# EXP02_04_2307_20232241110.net
KiCad netlist of a schematic drawn in Altium Designer
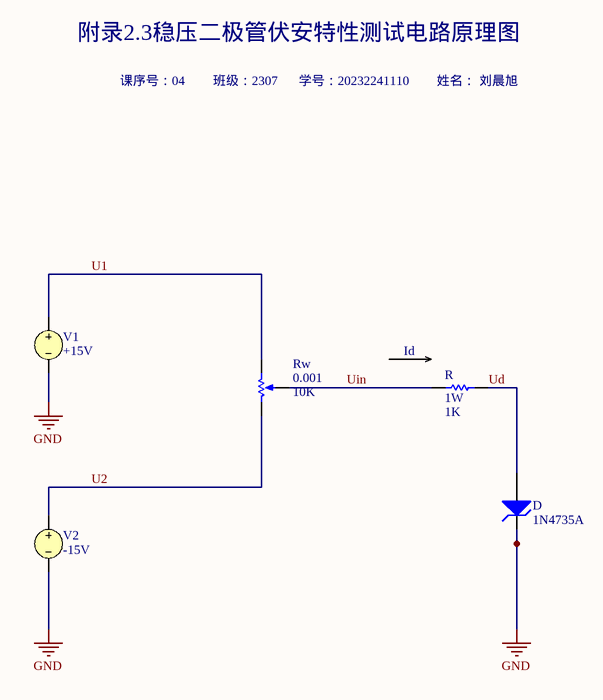
[diagram p0: EXP02_04_2307_20232241110.SchDoc]

(export (version "E")
  (design (tool "Eeschema 10.0.6"))
  (components
    (comp (ref "D")
      (value "1N4735A")
      (footprint "DO-41")
      (description "One Watt Zener")
      (fields (field (name "PUBLISHER") "Altium Limited"))
      (libsource (lib "FSC Discrete Diode") (part "1N4735A"))
    )
    (comp (ref "R")
      (value "1W")
      (footprint "AXIAL-0.3")
      (description "Resistor")
      (fields (field (name "ALTIUM_VALUE") "1K") (field (name "PUBLISHER") "Altium Limited"))
      (libsource (lib "Miscellaneous Devices") (part "Res1"))
    )
    (comp (ref "Rw")
      (value "10K")
      (footprint "VR5")
      (description "Potentiometer")
      (fields
        (field (name "SET POSITION") "0.001")
        (field (name "Comment") "RPot")
        (field (name "PUBLISHER") "Altium Limited")
      )
      (libsource (lib "Miscellaneous Devices") (part "RPot"))
    )
    (comp (ref "V1")
      (value "+15V")
      (description "Voltage Source")
      (fields (field (name "Comment") "VSRC") (field (name "PUBLISHER") "Altium Limited"))
      (libsource (lib "Simulation Sources") (part "VSRC"))
    )
    (comp (ref "V2")
      (value "-15V")
      (description "Voltage Source")
      (fields (field (name "Comment") "VSRC") (field (name "PUBLISHER") "Altium Limited"))
      (libsource (lib "Simulation Sources") (part "VSRC"))
    )
  )
  (nets
    (net (code "1") (name "/U1") (class "Default")
      (node (ref "Rw") (pin "1") (pinfunction "TOP_1") (pintype "passive"))
      (node (ref "V1") (pin "1") (pinfunction "1_1") (pintype "passive"))
    )
    (net (code "2") (name "/U2") (class "Default")
      (node (ref "Rw") (pin "2") (pinfunction "BOT_2") (pintype "passive"))
      (node (ref "V2") (pin "1") (pinfunction "1_1") (pintype "passive"))
    )
    (net (code "3") (name "/Ud") (class "Default")
      (node (ref "D") (pin "1") (pinfunction "A_1") (pintype "passive"))
      (node (ref "R") (pin "2") (pinfunction "2_2") (pintype "passive"))
    )
    (net (code "4") (name "/Uin") (class "Default")
      (node (ref "R") (pin "1") (pinfunction "1_1") (pintype "passive"))
      (node (ref "Rw") (pin "3") (pinfunction "TAP_3") (pintype "passive"))
    )
    (net (code "5") (name "GND") (class "Default")
      (node (ref "D") (pin "2") (pinfunction "K_2") (pintype "passive"))
      (node (ref "V1") (pin "2") (pinfunction "2_2") (pintype "passive"))
      (node (ref "V2") (pin "2") (pinfunction "2_2") (pintype "passive"))
    )
  )
)
